# drums.net
KiCad netlist of a schematic drawn in EAGLE
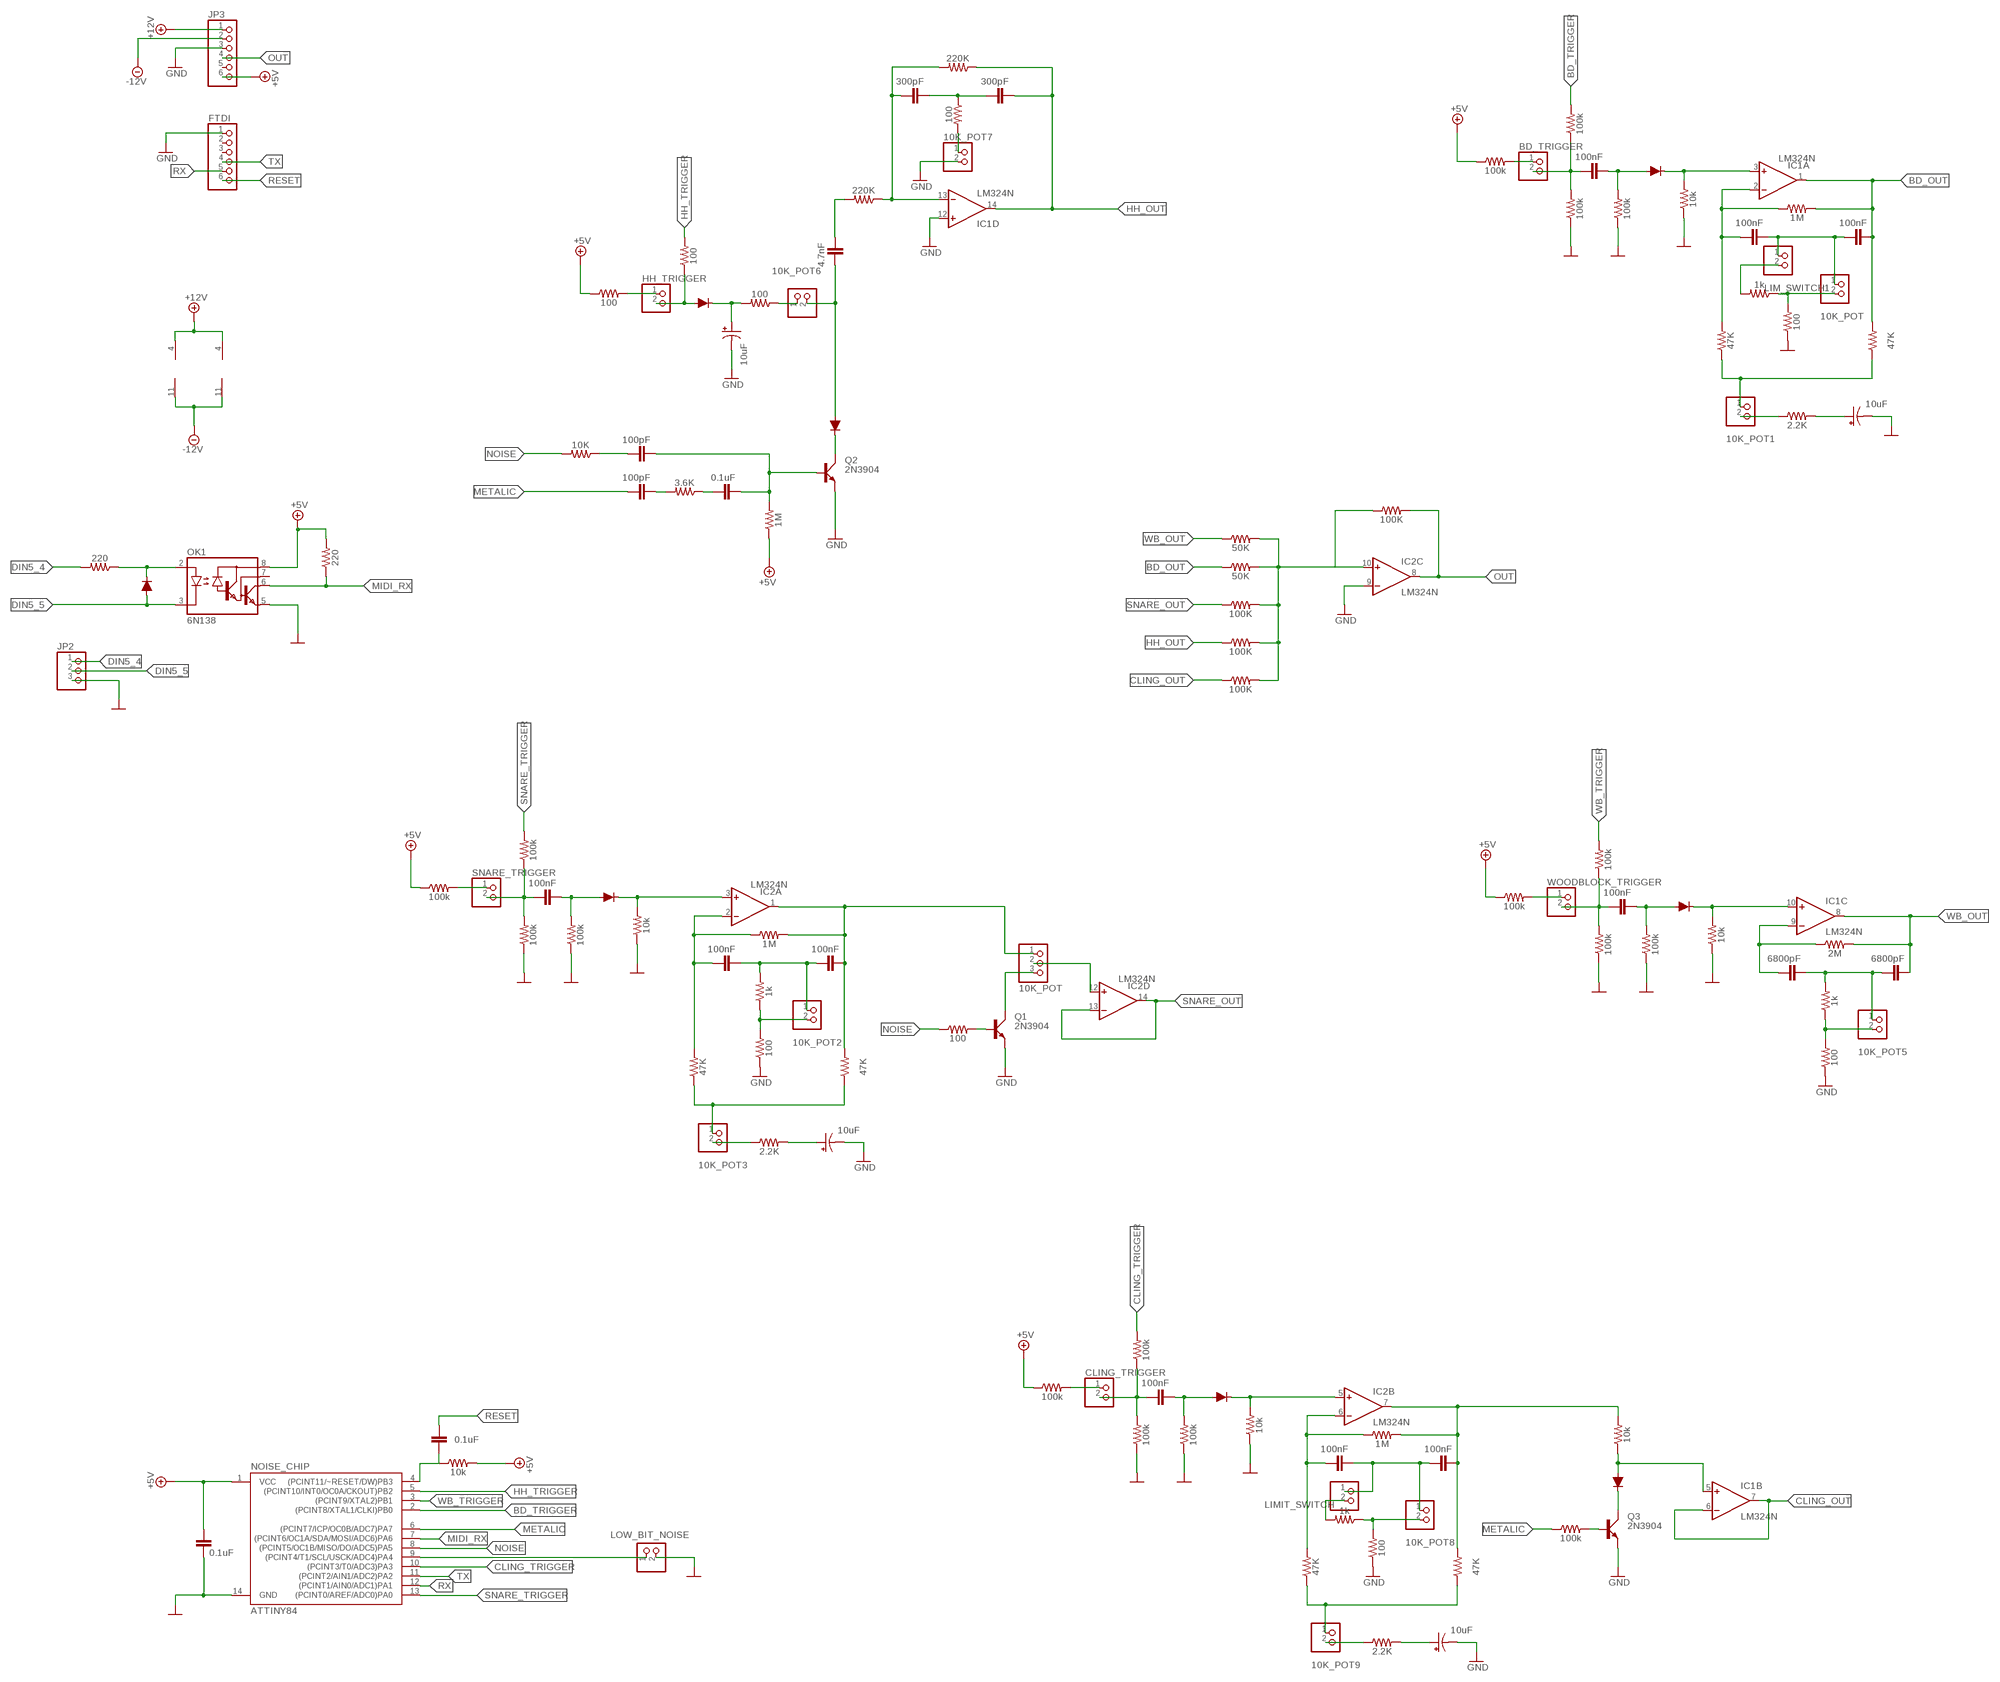
[diagram p0: schematic, sheet 1]

(export (version "E")
  (design (tool "Eeschema 10.0.6"))
  (components
    (comp (ref "1M")
      (value "1M")
      (footprint "eagle-import:AXIAL-0.3")
      (libsource (lib "eagle-import") (part "100KOHM-HORIZ-1/4W-5%"))
    )
    (comp (ref "1M1")
      (value "220")
      (footprint "eagle-import:AXIAL-0.3")
      (libsource (lib "eagle-import") (part "100KOHM-HORIZ-1/4W-5%"))
    )
    (comp (ref "1M2")
      (value "220")
      (footprint "eagle-import:AXIAL-0.3")
      (libsource (lib "eagle-import") (part "100KOHM-HORIZ-1/4W-5%"))
    )
    (comp (ref "10K_POT")
      (value "PINHD-1X2")
      (footprint "eagle-import:1X02")
      (libsource (lib "eagle-import") (part "PINHD-1X2"))
    )
    (comp (ref "10K_POT1")
      (value "PINHD-1X2")
      (footprint "eagle-import:1X02")
      (libsource (lib "eagle-import") (part "PINHD-1X2"))
    )
    (comp (ref "10K_POT2")
      (value "PINHD-1X2")
      (footprint "eagle-import:1X02")
      (libsource (lib "eagle-import") (part "PINHD-1X2"))
    )
    (comp (ref "10K_POT3")
      (value "PINHD-1X2")
      (footprint "eagle-import:1X02")
      (libsource (lib "eagle-import") (part "PINHD-1X2"))
    )
    (comp (ref "10K_POT4")
      (value "10K_POT")
      (footprint "eagle-import:1X03")
      (libsource (lib "eagle-import") (part "pinhead_325_PINHD-1X3"))
    )
    (comp (ref "10K_POT5")
      (value "PINHD-1X2")
      (footprint "eagle-import:1X02")
      (libsource (lib "eagle-import") (part "PINHD-1X2"))
    )
    (comp (ref "10K_POT6")
      (value "PINHD-1X2")
      (footprint "eagle-import:1X02")
      (libsource (lib "eagle-import") (part "PINHD-1X2"))
    )
    (comp (ref "10K_POT7")
      (value "PINHD-1X2")
      (footprint "eagle-import:1X02")
      (libsource (lib "eagle-import") (part "PINHD-1X2"))
    )
    (comp (ref "10K_POT8")
      (value "PINHD-1X2")
      (footprint "eagle-import:1X02")
      (libsource (lib "eagle-import") (part "PINHD-1X2"))
    )
    (comp (ref "10K_POT9")
      (value "PINHD-1X2")
      (footprint "eagle-import:1X02")
      (libsource (lib "eagle-import") (part "PINHD-1X2"))
    )
    (comp (ref "BD_TRIGGER")
      (value "PINHD-1X2")
      (footprint "eagle-import:1X02")
      (libsource (lib "eagle-import") (part "PINHD-1X2"))
    )
    (comp (ref "C1")
      (value "0.1uF")
      (footprint "eagle-import:C5B3")
      (libsource (lib "eagle-import") (part "C5/3"))
    )
    (comp (ref "C2")
      (value "100nF")
      (footprint "eagle-import:C5B3")
      (libsource (lib "eagle-import") (part "C5/3"))
    )
    (comp (ref "C3")
      (value "100nF")
      (footprint "eagle-import:C5B3")
      (libsource (lib "eagle-import") (part "C5/3"))
    )
    (comp (ref "C4")
      (value "0.1uF")
      (footprint "eagle-import:C5B3")
      (libsource (lib "eagle-import") (part "C5/3"))
    )
    (comp (ref "C5")
      (value "10uF")
      (footprint "eagle-import:TT5D11")
      (libsource (lib "eagle-import") (part "CPOL-USTT5D11"))
    )
    (comp (ref "C6")
      (value "100nF")
      (footprint "eagle-import:C5B3")
      (libsource (lib "eagle-import") (part "C5/3"))
    )
    (comp (ref "C7")
      (value "100nF")
      (footprint "eagle-import:C5B3")
      (libsource (lib "eagle-import") (part "C5/3"))
    )
    (comp (ref "C8")
      (value "10uF")
      (footprint "eagle-import:TT5D11")
      (libsource (lib "eagle-import") (part "CPOL-USTT5D11"))
    )
    (comp (ref "C9")
      (value "6800pF")
      (footprint "eagle-import:C5B3")
      (libsource (lib "eagle-import") (part "C5/3"))
    )
    (comp (ref "C10")
      (value "6800pF")
      (footprint "eagle-import:C5B3")
      (libsource (lib "eagle-import") (part "C5/3"))
    )
    (comp (ref "C11")
      (value "10uF")
      (footprint "eagle-import:TT5D11")
      (libsource (lib "eagle-import") (part "CPOL-USTT5D11"))
    )
    (comp (ref "C12")
      (value "0.1uF")
      (footprint "eagle-import:C5B3")
      (libsource (lib "eagle-import") (part "C5/3"))
    )
    (comp (ref "C13")
      (value "100pF")
      (footprint "eagle-import:C5B3")
      (libsource (lib "eagle-import") (part "C5/3"))
    )
    (comp (ref "C14")
      (value "100pF")
      (footprint "eagle-import:C5B3")
      (libsource (lib "eagle-import") (part "C5/3"))
    )
    (comp (ref "C15")
      (value "4.7nF")
      (footprint "eagle-import:C5B3")
      (libsource (lib "eagle-import") (part "C5/3"))
    )
    (comp (ref "C16")
      (value "300pF")
      (footprint "eagle-import:C5B3")
      (libsource (lib "eagle-import") (part "C5/3"))
    )
    (comp (ref "C17")
      (value "300pF")
      (footprint "eagle-import:C5B3")
      (libsource (lib "eagle-import") (part "C5/3"))
    )
    (comp (ref "C18")
      (value "100nF")
      (footprint "eagle-import:C5B3")
      (libsource (lib "eagle-import") (part "C5/3"))
    )
    (comp (ref "C19")
      (value "100nF")
      (footprint "eagle-import:C5B3")
      (libsource (lib "eagle-import") (part "C5/3"))
    )
    (comp (ref "C20")
      (value "100nF")
      (footprint "eagle-import:C5B3")
      (libsource (lib "eagle-import") (part "C5/3"))
    )
    (comp (ref "C21")
      (value "100nF")
      (footprint "eagle-import:C5B3")
      (libsource (lib "eagle-import") (part "C5/3"))
    )
    (comp (ref "C22")
      (value "100nF")
      (footprint "eagle-import:C5B3")
      (libsource (lib "eagle-import") (part "C5/3"))
    )
    (comp (ref "C23")
      (value "10uF")
      (footprint "eagle-import:TT5D11")
      (libsource (lib "eagle-import") (part "CPOL-USTT5D11"))
    )
    (comp (ref "C24")
      (value "100nF")
      (footprint "eagle-import:C5B3")
      (libsource (lib "eagle-import") (part "C5/3"))
    )
    (comp (ref "CLING_TRIGGER")
      (value "PINHD-1X2")
      (footprint "eagle-import:1X02")
      (libsource (lib "eagle-import") (part "PINHD-1X2"))
    )
    (comp (ref "D1")
      (value "1A/50V/1.1V")
      (footprint "eagle-import:DIODE-1N4001-KIT")
      (libsource (lib "eagle-import") (part "DIODE-KIT2"))
    )
    (comp (ref "D2")
      (value "1A/50V/1.1V")
      (footprint "eagle-import:DIODE-1N4001-KIT")
      (libsource (lib "eagle-import") (part "DIODE-KIT2"))
    )
    (comp (ref "D3")
      (value "1A/50V/1.1V")
      (footprint "eagle-import:DIODE-1N4001-KIT")
      (libsource (lib "eagle-import") (part "DIODE-KIT2"))
    )
    (comp (ref "D4")
      (value "1A/50V/1.1V")
      (footprint "eagle-import:DIODE-1N4001-KIT")
      (libsource (lib "eagle-import") (part "DIODE-KIT2"))
    )
    (comp (ref "D5")
      (value "1A/50V/1.1V")
      (footprint "eagle-import:DIODE-1N4001-KIT")
      (libsource (lib "eagle-import") (part "DIODE-KIT2"))
    )
    (comp (ref "D6")
      (value "1A/50V/1.1V")
      (footprint "eagle-import:DIODE-1N4001-KIT")
      (libsource (lib "eagle-import") (part "DIODE-KIT2"))
    )
    (comp (ref "D7")
      (value "1A/50V/1.1V")
      (footprint "eagle-import:DIODE-1N4001-KIT")
      (libsource (lib "eagle-import") (part "DIODE-KIT2"))
    )
    (comp (ref "D8")
      (value "1A/50V/1.1V")
      (footprint "eagle-import:DIODE-1N4001-KIT")
      (libsource (lib "eagle-import") (part "DIODE-KIT2"))
    )
    (comp (ref "FTDI")
      (value "PINHD-1X6")
      (footprint "eagle-import:1X06")
      (libsource (lib "eagle-import") (part "PINHD-1X6"))
    )
    (comp (ref "HH_TRIGGER")
      (value "PINHD-1X2")
      (footprint "eagle-import:1X02")
      (libsource (lib "eagle-import") (part "PINHD-1X2"))
    )
    (comp (ref "IC1")
      (value "LM324N")
      (footprint "eagle-import:DIL14")
      (libsource (lib "eagle-import") (part "LM324N"))
    )
    (comp (ref "IC2")
      (value "LM324N")
      (footprint "eagle-import:DIL14")
      (libsource (lib "eagle-import") (part "LM324N"))
    )
    (comp (ref "JP2")
      (value "PINHD-1X3")
      (footprint "eagle-import:1X03")
      (libsource (lib "eagle-import") (part "PINHD-1X3"))
    )
    (comp (ref "JP3")
      (value "PINHD-1X6")
      (footprint "eagle-import:1X06")
      (libsource (lib "eagle-import") (part "PINHD-1X6"))
    )
    (comp (ref "LIMIT_SWITCH")
      (value "PINHD-1X2")
      (footprint "eagle-import:1X02")
      (libsource (lib "eagle-import") (part "PINHD-1X2"))
    )
    (comp (ref "LIM_SWITCH1")
      (value "PINHD-1X2")
      (footprint "eagle-import:1X02")
      (libsource (lib "eagle-import") (part "PINHD-1X2"))
    )
    (comp (ref "LOW_BIT_NOISE")
      (value "PINHD-1X2")
      (footprint "eagle-import:1X02")
      (libsource (lib "eagle-import") (part "PINHD-1X2"))
    )
    (comp (ref "NOISE_CHIP")
      (value "ATTINY84")
      (footprint "eagle-import:DIP14")
      (libsource (lib "eagle-import") (part "ATTINY84ATTINY84-20PU"))
    )
    (comp (ref "OK1")
      (value "6N138")
      (footprint "eagle-import:DIL08")
      (fields (field (name "MF") "VISHAY/TELEFUNKEN"))
      (libsource (lib "eagle-import") (part "6N138"))
    )
    (comp (ref "Q1")
      (value "2N3904")
      (footprint "eagle-import:TO92D")
      (libsource (lib "eagle-import") (part "2N3904"))
    )
    (comp (ref "Q2")
      (value "2N3904")
      (footprint "eagle-import:TO92D")
      (libsource (lib "eagle-import") (part "2N3904"))
    )
    (comp (ref "Q3")
      (value "2N3904")
      (footprint "eagle-import:TO92D")
      (libsource (lib "eagle-import") (part "2N3904"))
    )
    (comp (ref "R1")
      (value "100k")
      (footprint "eagle-import:AXIAL-0.3")
      (libsource (lib "eagle-import") (part "100KOHM-HORIZ-1/4W-5%"))
    )
    (comp (ref "R2")
      (value "10k")
      (footprint "eagle-import:AXIAL-0.3")
      (libsource (lib "eagle-import") (part "100KOHM-HORIZ-1/4W-5%"))
    )
    (comp (ref "R3")
      (value "1M")
      (footprint "eagle-import:AXIAL-0.3")
      (libsource (lib "eagle-import") (part "100KOHM-HORIZ-1/4W-5%"))
    )
    (comp (ref "R4")
      (value "47K")
      (footprint "eagle-import:AXIAL-0.3")
      (libsource (lib "eagle-import") (part "100KOHM-HORIZ-1/4W-5%"))
    )
    (comp (ref "R5")
      (value "47K")
      (footprint "eagle-import:AXIAL-0.3")
      (libsource (lib "eagle-import") (part "100KOHM-HORIZ-1/4W-5%"))
    )
    (comp (ref "R6")
      (value "1k")
      (footprint "eagle-import:AXIAL-0.3")
      (libsource (lib "eagle-import") (part "100KOHM-HORIZ-1/4W-5%"))
    )
    (comp (ref "R7")
      (value "100")
      (footprint "eagle-import:AXIAL-0.3")
      (libsource (lib "eagle-import") (part "100KOHM-HORIZ-1/4W-5%"))
    )
    (comp (ref "R8")
      (value "2.2K")
      (footprint "eagle-import:AXIAL-0.3")
      (libsource (lib "eagle-import") (part "100KOHM-HORIZ-1/4W-5%"))
    )
    (comp (ref "R9")
      (value "50K")
      (footprint "eagle-import:AXIAL-0.3")
      (libsource (lib "eagle-import") (part "100KOHM-HORIZ-1/4W-5%"))
    )
    (comp (ref "R10")
      (value "100K")
      (footprint "eagle-import:AXIAL-0.3")
      (libsource (lib "eagle-import") (part "100KOHM-HORIZ-1/4W-5%"))
    )
    (comp (ref "R11")
      (value "100")
      (footprint "eagle-import:AXIAL-0.3")
      (libsource (lib "eagle-import") (part "100KOHM-HORIZ-1/4W-5%"))
    )
    (comp (ref "R12")
      (value "100k")
      (footprint "eagle-import:AXIAL-0.3")
      (libsource (lib "eagle-import") (part "100KOHM-HORIZ-1/4W-5%"))
    )
    (comp (ref "R13")
      (value "1M")
      (footprint "eagle-import:AXIAL-0.3")
      (libsource (lib "eagle-import") (part "100KOHM-HORIZ-1/4W-5%"))
    )
    (comp (ref "R14")
      (value "47K")
      (footprint "eagle-import:AXIAL-0.3")
      (libsource (lib "eagle-import") (part "100KOHM-HORIZ-1/4W-5%"))
    )
    (comp (ref "R15")
      (value "47K")
      (footprint "eagle-import:AXIAL-0.3")
      (libsource (lib "eagle-import") (part "100KOHM-HORIZ-1/4W-5%"))
    )
    (comp (ref "R16")
      (value "1k")
      (footprint "eagle-import:AXIAL-0.3")
      (libsource (lib "eagle-import") (part "100KOHM-HORIZ-1/4W-5%"))
    )
    (comp (ref "R17")
      (value "100")
      (footprint "eagle-import:AXIAL-0.3")
      (libsource (lib "eagle-import") (part "100KOHM-HORIZ-1/4W-5%"))
    )
    (comp (ref "R18")
      (value "2.2K")
      (footprint "eagle-import:AXIAL-0.3")
      (libsource (lib "eagle-import") (part "100KOHM-HORIZ-1/4W-5%"))
    )
    (comp (ref "R19")
      (value "100k")
      (footprint "eagle-import:AXIAL-0.3")
      (libsource (lib "eagle-import") (part "100KOHM-HORIZ-1/4W-5%"))
    )
    (comp (ref "R20")
      (value "100k")
      (footprint "eagle-import:AXIAL-0.3")
      (libsource (lib "eagle-import") (part "100KOHM-HORIZ-1/4W-5%"))
    )
    (comp (ref "R21")
      (value "100")
      (footprint "eagle-import:AXIAL-0.3")
      (libsource (lib "eagle-import") (part "100KOHM-HORIZ-1/4W-5%"))
    )
    (comp (ref "R22")
      (value "10k")
      (footprint "eagle-import:AXIAL-0.3")
      (libsource (lib "eagle-import") (part "100KOHM-HORIZ-1/4W-5%"))
    )
    (comp (ref "R23")
      (value "100k")
      (footprint "eagle-import:AXIAL-0.3")
      (libsource (lib "eagle-import") (part "100KOHM-HORIZ-1/4W-5%"))
    )
    (comp (ref "R24")
      (value "2M")
      (footprint "eagle-import:AXIAL-0.3")
      (libsource (lib "eagle-import") (part "100KOHM-HORIZ-1/4W-5%"))
    )
    (comp (ref "R25")
      (value "10k")
      (footprint "eagle-import:AXIAL-0.3")
      (libsource (lib "eagle-import") (part "100KOHM-HORIZ-1/4W-5%"))
    )
    (comp (ref "R26")
      (value "100")
      (footprint "eagle-import:AXIAL-0.3")
      (libsource (lib "eagle-import") (part "100KOHM-HORIZ-1/4W-5%"))
    )
    (comp (ref "R27")
      (value "1k")
      (footprint "eagle-import:AXIAL-0.3")
      (libsource (lib "eagle-import") (part "100KOHM-HORIZ-1/4W-5%"))
    )
    (comp (ref "R28")
      (value "100")
      (footprint "eagle-import:AXIAL-0.3")
      (libsource (lib "eagle-import") (part "100KOHM-HORIZ-1/4W-5%"))
    )
    (comp (ref "R29")
      (value "100")
      (footprint "eagle-import:AXIAL-0.3")
      (libsource (lib "eagle-import") (part "100KOHM-HORIZ-1/4W-5%"))
    )
    (comp (ref "R30")
      (value "100K")
      (footprint "eagle-import:AXIAL-0.3")
      (libsource (lib "eagle-import") (part "100KOHM-HORIZ-1/4W-5%"))
    )
    (comp (ref "R31")
      (value "50K")
      (footprint "eagle-import:AXIAL-0.3")
      (libsource (lib "eagle-import") (part "100KOHM-HORIZ-1/4W-5%"))
    )
    (comp (ref "R32")
      (value "3.6K")
      (footprint "eagle-import:AXIAL-0.3")
      (libsource (lib "eagle-import") (part "100KOHM-HORIZ-1/4W-5%"))
    )
    (comp (ref "R33")
      (value "10K")
      (footprint "eagle-import:AXIAL-0.3")
      (libsource (lib "eagle-import") (part "100KOHM-HORIZ-1/4W-5%"))
    )
    (comp (ref "R34")
      (value "220K")
      (footprint "eagle-import:AXIAL-0.3")
      (libsource (lib "eagle-import") (part "100KOHM-HORIZ-1/4W-5%"))
    )
    (comp (ref "R35")
      (value "220K")
      (footprint "eagle-import:AXIAL-0.3")
      (libsource (lib "eagle-import") (part "100KOHM-HORIZ-1/4W-5%"))
    )
    (comp (ref "R36")
      (value "100")
      (footprint "eagle-import:AXIAL-0.3")
      (libsource (lib "eagle-import") (part "100KOHM-HORIZ-1/4W-5%"))
    )
    (comp (ref "R37")
      (value "100K")
      (footprint "eagle-import:AXIAL-0.3")
      (libsource (lib "eagle-import") (part "100KOHM-HORIZ-1/4W-5%"))
    )
    (comp (ref "R38")
      (value "100k")
      (footprint "eagle-import:AXIAL-0.3")
      (libsource (lib "eagle-import") (part "100KOHM-HORIZ-1/4W-5%"))
    )
    (comp (ref "R39")
      (value "100k")
      (footprint "eagle-import:AXIAL-0.3")
      (libsource (lib "eagle-import") (part "100KOHM-HORIZ-1/4W-5%"))
    )
    (comp (ref "R40")
      (value "10k")
      (footprint "eagle-import:AXIAL-0.3")
      (libsource (lib "eagle-import") (part "100KOHM-HORIZ-1/4W-5%"))
    )
    (comp (ref "R41")
      (value "100k")
      (footprint "eagle-import:AXIAL-0.3")
      (libsource (lib "eagle-import") (part "100KOHM-HORIZ-1/4W-5%"))
    )
    (comp (ref "R42")
      (value "100k")
      (footprint "eagle-import:AXIAL-0.3")
      (libsource (lib "eagle-import") (part "100KOHM-HORIZ-1/4W-5%"))
    )
    (comp (ref "R43")
      (value "100k")
      (footprint "eagle-import:AXIAL-0.3")
      (libsource (lib "eagle-import") (part "100KOHM-HORIZ-1/4W-5%"))
    )
    (comp (ref "R44")
      (value "100k")
      (footprint "eagle-import:AXIAL-0.3")
      (libsource (lib "eagle-import") (part "100KOHM-HORIZ-1/4W-5%"))
    )
    (comp (ref "R45")
      (value "100k")
      (footprint "eagle-import:AXIAL-0.3")
      (libsource (lib "eagle-import") (part "100KOHM-HORIZ-1/4W-5%"))
    )
    (comp (ref "R46")
      (value "1M")
      (footprint "eagle-import:AXIAL-0.3")
      (libsource (lib "eagle-import") (part "100KOHM-HORIZ-1/4W-5%"))
    )
    (comp (ref "R47")
      (value "47K")
      (footprint "eagle-import:AXIAL-0.3")
      (libsource (lib "eagle-import") (part "100KOHM-HORIZ-1/4W-5%"))
    )
    (comp (ref "R48")
      (value "47K")
      (footprint "eagle-import:AXIAL-0.3")
      (libsource (lib "eagle-import") (part "100KOHM-HORIZ-1/4W-5%"))
    )
    (comp (ref "R49")
      (value "1k")
      (footprint "eagle-import:AXIAL-0.3")
      (libsource (lib "eagle-import") (part "100KOHM-HORIZ-1/4W-5%"))
    )
    (comp (ref "R50")
      (value "100")
      (footprint "eagle-import:AXIAL-0.3")
      (libsource (lib "eagle-import") (part "100KOHM-HORIZ-1/4W-5%"))
    )
    (comp (ref "R51")
      (value "2.2K")
      (footprint "eagle-import:AXIAL-0.3")
      (libsource (lib "eagle-import") (part "100KOHM-HORIZ-1/4W-5%"))
    )
    (comp (ref "R52")
      (value "100k")
      (footprint "eagle-import:AXIAL-0.3")
      (libsource (lib "eagle-import") (part "100KOHM-HORIZ-1/4W-5%"))
    )
    (comp (ref "R53")
      (value "10k")
      (footprint "eagle-import:AXIAL-0.3")
      (libsource (lib "eagle-import") (part "100KOHM-HORIZ-1/4W-5%"))
    )
    (comp (ref "R54")
      (value "100k")
      (footprint "eagle-import:AXIAL-0.3")
      (libsource (lib "eagle-import") (part "100KOHM-HORIZ-1/4W-5%"))
    )
    (comp (ref "R55")
      (value "100k")
      (footprint "eagle-import:AXIAL-0.3")
      (libsource (lib "eagle-import") (part "100KOHM-HORIZ-1/4W-5%"))
    )
    (comp (ref "R56")
      (value "100k")
      (footprint "eagle-import:AXIAL-0.3")
      (libsource (lib "eagle-import") (part "100KOHM-HORIZ-1/4W-5%"))
    )
    (comp (ref "R57")
      (value "100k")
      (footprint "eagle-import:AXIAL-0.3")
      (libsource (lib "eagle-import") (part "100KOHM-HORIZ-1/4W-5%"))
    )
    (comp (ref "R58")
      (value "100K")
      (footprint "eagle-import:AXIAL-0.3")
      (libsource (lib "eagle-import") (part "100KOHM-HORIZ-1/4W-5%"))
    )
    (comp (ref "R59")
      (value "10k")
      (footprint "eagle-import:AXIAL-0.3")
      (libsource (lib "eagle-import") (part "100KOHM-HORIZ-1/4W-5%"))
    )
    (comp (ref "SNARE_TRIGGER")
      (value "PINHD-1X2")
      (footprint "eagle-import:1X02")
      (libsource (lib "eagle-import") (part "PINHD-1X2"))
    )
    (comp (ref "WOODBLOCK_TRIGGER")
      (value "PINHD-1X2")
      (footprint "eagle-import:1X02")
      (libsource (lib "eagle-import") (part "PINHD-1X2"))
    )
  )
  (nets
    (net (code "1") (name "+5V") (class "Default")
      (node (ref "1M") (pin "P$1") (pinfunction "1_P$1") (pintype "passive"))
      (node (ref "1M1") (pin "P$2") (pinfunction "2_P$2") (pintype "passive"))
      (node (ref "C1") (pin "1") (pinfunction "1_1") (pintype "passive"))
      (node (ref "JP3") (pin "6") (pinfunction "6_6") (pintype "passive"))
      (node (ref "NOISE_CHIP") (pin "1") (pinfunction "VCC_1") (pintype "bidirectional"))
      (node (ref "OK1") (pin "8") (pinfunction "VCC_8") (pintype "passive"))
      (node (ref "R23") (pin "P$1") (pinfunction "1_P$1") (pintype "passive"))
      (node (ref "R25") (pin "P$2") (pinfunction "2_P$2") (pintype "passive"))
      (node (ref "R29") (pin "P$1") (pinfunction "1_P$1") (pintype "passive"))
      (node (ref "R38") (pin "P$1") (pinfunction "1_P$1") (pintype "passive"))
      (node (ref "R41") (pin "P$1") (pinfunction "1_P$1") (pintype "passive"))
      (node (ref "R54") (pin "P$1") (pinfunction "1_P$1") (pintype "passive"))
    )
    (net (code "2") (name "+12V") (class "Default")
      (node (ref "IC1") (pin "4") (pinfunction "V+_4") (pintype "power_in"))
      (node (ref "IC2") (pin "4") (pinfunction "V+_4") (pintype "power_in"))
      (node (ref "JP3") (pin "1") (pinfunction "1_1") (pintype "passive"))
    )
    (net (code "3") (name "-12V") (class "Default")
      (node (ref "IC1") (pin "11") (pinfunction "V-_11") (pintype "power_in"))
      (node (ref "IC2") (pin "11") (pinfunction "V-_11") (pintype "power_in"))
      (node (ref "JP3") (pin "2") (pinfunction "2_2") (pintype "passive"))
    )
    (net (code "4") (name "BD_OUT") (class "Default")
      (node (ref "10K_POT4") (pin "1") (pinfunction "1_1") (pintype "passive"))
      (node (ref "C3") (pin "2") (pinfunction "2_2") (pintype "passive"))
      (node (ref "C7") (pin "2") (pinfunction "2_2") (pintype "passive"))
      (node (ref "IC1") (pin "1") (pinfunction "OUT_1") (pintype "output"))
      (node (ref "IC2") (pin "1") (pinfunction "OUT_1") (pintype "output"))
      (node (ref "R13") (pin "P$2") (pinfunction "2_P$2") (pintype "passive"))
      (node (ref "R15") (pin "P$2") (pinfunction "2_P$2") (pintype "passive"))
      (node (ref "R3") (pin "P$2") (pinfunction "2_P$2") (pintype "passive"))
      (node (ref "R31") (pin "P$1") (pinfunction "1_P$1") (pintype "passive"))
      (node (ref "R5") (pin "P$2") (pinfunction "2_P$2") (pintype "passive"))
    )
    (net (code "5") (name "BD_TRIGGER") (class "Default")
      (node (ref "NOISE_CHIP") (pin "2") (pinfunction "(PCINT8/XTAL1/CLKI)PB0_2") (pintype "bidirectional"))
      (node (ref "R12") (pin "P$2") (pinfunction "2_P$2") (pintype "passive"))
    )
    (net (code "6") (name "CLING_OUT") (class "Default")
      (node (ref "IC1") (pin "6") (pinfunction "-IN_6") (pintype "input"))
      (node (ref "IC1") (pin "7") (pinfunction "OUT_7") (pintype "output"))
      (node (ref "R58") (pin "P$1") (pinfunction "1_P$1") (pintype "passive"))
    )
    (net (code "7") (name "CLING_TRIGGER") (class "Default")
      (node (ref "NOISE_CHIP") (pin "10") (pinfunction "(PCINT3/T0/ADC3)PA3_10") (pintype "bidirectional"))
      (node (ref "R57") (pin "P$2") (pinfunction "2_P$2") (pintype "passive"))
    )
    (net (code "8") (name "DIN5_4") (class "Default")
      (node (ref "1M2") (pin "P$2") (pinfunction "2_P$2") (pintype "passive"))
      (node (ref "JP2") (pin "1") (pinfunction "1_1") (pintype "passive"))
    )
    (net (code "9") (name "DIN5_5") (class "Default")
      (node (ref "D2") (pin "A") (pinfunction "A_A") (pintype "passive"))
      (node (ref "JP2") (pin "2") (pinfunction "2_2") (pintype "passive"))
      (node (ref "OK1") (pin "3") (pinfunction "C_3") (pintype "passive"))
    )
    (net (code "10") (name "GND") (class "Default")
      (node (ref "10K_POT7") (pin "2") (pinfunction "2_2") (pintype "passive"))
      (node (ref "C1") (pin "2") (pinfunction "2_2") (pintype "passive"))
      (node (ref "C11") (pin "-") (pinfunction "-_-") (pintype "passive"))
      (node (ref "C23") (pin "-") (pinfunction "-_-") (pintype "passive"))
      (node (ref "C5") (pin "-") (pinfunction "-_-") (pintype "passive"))
      (node (ref "C8") (pin "-") (pinfunction "-_-") (pintype "passive"))
      (node (ref "FTDI") (pin "1") (pinfunction "1_1") (pintype "passive"))
      (node (ref "IC1") (pin "12") (pinfunction "+IN_12") (pintype "input"))
      (node (ref "IC2") (pin "9") (pinfunction "-IN_9") (pintype "input"))
      (node (ref "JP2") (pin "3") (pinfunction "3_3") (pintype "passive"))
      (node (ref "JP3") (pin "3") (pinfunction "3_3") (pintype "passive"))
      (node (ref "LOW_BIT_NOISE") (pin "2") (pinfunction "2_2") (pintype "passive"))
      (node (ref "NOISE_CHIP") (pin "14") (pinfunction "GND_14") (pintype "bidirectional"))
      (node (ref "OK1") (pin "5") (pinfunction "GND_5") (pintype "passive"))
      (node (ref "Q1") (pin "E") (pinfunction "E_E") (pintype "passive"))
      (node (ref "Q2") (pin "E") (pinfunction "E_E") (pintype "passive"))
      (node (ref "Q3") (pin "E") (pinfunction "E_E") (pintype "passive"))
      (node (ref "R1") (pin "P$1") (pinfunction "1_P$1") (pintype "passive"))
      (node (ref "R17") (pin "P$1") (pinfunction "1_P$1") (pintype "passive"))
      (node (ref "R2") (pin "P$1") (pinfunction "1_P$1") (pintype "passive"))
      (node (ref "R22") (pin "P$1") (pinfunction "1_P$1") (pintype "passive"))
      (node (ref "R28") (pin "P$1") (pinfunction "1_P$1") (pintype "passive"))
      (node (ref "R39") (pin "P$1") (pinfunction "1_P$1") (pintype "passive"))
      (node (ref "R40") (pin "P$1") (pinfunction "1_P$1") (pintype "passive"))
      (node (ref "R42") (pin "P$1") (pinfunction "1_P$1") (pintype "passive"))
      (node (ref "R43") (pin "P$1") (pinfunction "1_P$1") (pintype "passive"))
      (node (ref "R44") (pin "P$1") (pinfunction "1_P$1") (pintype "passive"))
      (node (ref "R45") (pin "P$1") (pinfunction "1_P$1") (pintype "passive"))
      (node (ref "R50") (pin "P$1") (pinfunction "1_P$1") (pintype "passive"))
      (node (ref "R53") (pin "P$1") (pinfunction "1_P$1") (pintype "passive"))
      (node (ref "R55") (pin "P$1") (pinfunction "1_P$1") (pintype "passive"))
      (node (ref "R56") (pin "P$1") (pinfunction "1_P$1") (pintype "passive"))
      (node (ref "R7") (pin "P$1") (pinfunction "1_P$1") (pintype "passive"))
    )
    (net (code "11") (name "HH_OUT") (class "Default")
      (node (ref "C17") (pin "2") (pinfunction "2_2") (pintype "passive"))
      (node (ref "IC1") (pin "14") (pinfunction "OUT_14") (pintype "output"))
      (node (ref "R35") (pin "P$1") (pinfunction "1_P$1") (pintype "passive"))
      (node (ref "R37") (pin "P$1") (pinfunction "1_P$1") (pintype "passive"))
    )
    (net (code "12") (name "HH_TRIGGER") (class "Default")
      (node (ref "NOISE_CHIP") (pin "5") (pinfunction "(PCINT10/INT0/OC0A/CKOUT)PB2_5") (pintype "bidirectional"))
      (node (ref "R11") (pin "P$2") (pinfunction "2_P$2") (pintype "passive"))
    )
    (net (code "13") (name "METALIC") (class "Default")
      (node (ref "C14") (pin "1") (pinfunction "1_1") (pintype "passive"))
      (node (ref "NOISE_CHIP") (pin "6") (pinfunction "(PCINT7/ICP/OC0B/ADC7)PA7_6") (pintype "bidirectional"))
      (node (ref "R52") (pin "P$1") (pinfunction "1_P$1") (pintype "passive"))
    )
    (net (code "14") (name "MIDI_RX") (class "Default")
      (node (ref "1M1") (pin "P$1") (pinfunction "1_P$1") (pintype "passive"))
      (node (ref "NOISE_CHIP") (pin "7") (pinfunction "(PCINT6/OC1A/SDA/MOSI/ADC6)PA6_7") (pintype "bidirectional"))
      (node (ref "OK1") (pin "6") (pinfunction "VO_6") (pintype "passive"))
    )
    (net (code "15") (name "NOISE") (class "Default")
      (node (ref "NOISE_CHIP") (pin "8") (pinfunction "(PCINT5/OC1B/MISO/DO/ADC5)PA5_8") (pintype "bidirectional"))
      (node (ref "R21") (pin "P$1") (pinfunction "1_P$1") (pintype "passive"))
      (node (ref "R33") (pin "P$2") (pinfunction "2_P$2") (pintype "passive"))
    )
    (net (code "16") (name "Net-(1M-2)") (class "Default")
      (node (ref "1M") (pin "P$2") (pinfunction "2_P$2") (pintype "passive"))
      (node (ref "C12") (pin "2") (pinfunction "2_2") (pintype "passive"))
      (node (ref "C13") (pin "2") (pinfunction "2_2") (pintype "passive"))
      (node (ref "Q2") (pin "B") (pinfunction "B_B") (pintype "passive"))
    )
    (net (code "17") (name "Net-(1M2-1)") (class "Default")
      (node (ref "1M2") (pin "P$1") (pinfunction "1_P$1") (pintype "passive"))
      (node (ref "D2") (pin "C") (pinfunction "C_C") (pintype "passive"))
      (node (ref "OK1") (pin "2") (pinfunction "A_2") (pintype "passive"))
    )
    (net (code "18") (name "Net-(10K_POT-Pad1)") (class "Default")
      (node (ref "10K_POT") (pin "1") (pinfunction "1_1") (pintype "passive"))
      (node (ref "C2") (pin "2") (pinfunction "2_2") (pintype "passive"))
      (node (ref "C3") (pin "1") (pinfunction "1_1") (pintype "passive"))
      (node (ref "LIM_SWITCH1") (pin "1") (pinfunction "1_1") (pintype "passive"))
    )
    (net (code "19") (name "Net-(10K_POT4-Pad3)") (class "Default")
      (node (ref "10K_POT4") (pin "3") (pinfunction "3_3") (pintype "passive"))
      (node (ref "Q1") (pin "C") (pinfunction "C_C") (pintype "passive"))
    )
    (net (code "20") (name "Net-(10K_POT6-Pad2)") (class "Default")
      (node (ref "10K_POT6") (pin "2") (pinfunction "2_2") (pintype "passive"))
      (node (ref "C15") (pin "1") (pinfunction "1_1") (pintype "passive"))
      (node (ref "D5") (pin "A") (pinfunction "A_A") (pintype "passive"))
    )
    (net (code "21") (name "Net-(10K_POT8-Pad1)") (class "Default")
      (node (ref "10K_POT8") (pin "1") (pinfunction "1_1") (pintype "passive"))
      (node (ref "C21") (pin "2") (pinfunction "2_2") (pintype "passive"))
      (node (ref "C22") (pin "1") (pinfunction "1_1") (pintype "passive"))
      (node (ref "LIMIT_SWITCH") (pin "1") (pinfunction "1_1") (pintype "passive"))
    )
    (net (code "22") (name "Net-(D5-PadC)") (class "Default")
      (node (ref "D5") (pin "C") (pinfunction "C_C") (pintype "passive"))
      (node (ref "Q2") (pin "C") (pinfunction "C_C") (pintype "passive"))
    )
    (net (code "23") (name "Net-(D8-PadC)") (class "Default")
      (node (ref "D8") (pin "C") (pinfunction "C_C") (pintype "passive"))
      (node (ref "Q3") (pin "C") (pinfunction "C_C") (pintype "passive"))
    )
    (net (code "24") (name "Net-(IC1A-+IN)") (class "Default")
      (node (ref "D1") (pin "C") (pinfunction "C_C") (pintype "passive"))
      (node (ref "IC1") (pin "3") (pinfunction "+IN_3") (pintype "input"))
      (node (ref "R2") (pin "P$2") (pinfunction "2_P$2") (pintype "passive"))
    )
    (net (code "25") (name "Net-(IC1A--IN)") (class "Default")
      (node (ref "C2") (pin "1") (pinfunction "1_1") (pintype "passive"))
      (node (ref "IC1") (pin "2") (pinfunction "-IN_2") (pintype "input"))
      (node (ref "R3") (pin "P$1") (pinfunction "1_P$1") (pintype "passive"))
      (node (ref "R4") (pin "P$2") (pinfunction "2_P$2") (pintype "passive"))
    )
    (net (code "26") (name "Net-(IC1B-+IN)") (class "Default")
      (node (ref "D8") (pin "A") (pinfunction "A_A") (pintype "passive"))
      (node (ref "IC1") (pin "5") (pinfunction "+IN_5") (pintype "input"))
      (node (ref "R59") (pin "P$1") (pinfunction "1_P$1") (pintype "passive"))
    )
    (net (code "27") (name "Net-(IC1C-+IN)") (class "Default")
      (node (ref "D6") (pin "C") (pinfunction "C_C") (pintype "passive"))
      (node (ref "IC1") (pin "10") (pinfunction "+IN_10") (pintype "input"))
      (node (ref "R40") (pin "P$2") (pinfunction "2_P$2") (pintype "passive"))
    )
    (net (code "28") (name "Net-(IC1C--IN)") (class "Default")
      (node (ref "C9") (pin "1") (pinfunction "1_1") (pintype "passive"))
      (node (ref "IC1") (pin "9") (pinfunction "-IN_9") (pintype "input"))
      (node (ref "R24") (pin "P$1") (pinfunction "1_P$1") (pintype "passive"))
    )
    (net (code "29") (name "Net-(IC1D--IN)") (class "Default")
      (node (ref "C16") (pin "1") (pinfunction "1_1") (pintype "passive"))
      (node (ref "IC1") (pin "13") (pinfunction "-IN_13") (pintype "input"))
      (node (ref "R34") (pin "P$1") (pinfunction "1_P$1") (pintype "passive"))
      (node (ref "R35") (pin "P$2") (pinfunction "2_P$2") (pintype "passive"))
    )
    (net (code "30") (name "Net-(IC2A-+IN)") (class "Default")
      (node (ref "D3") (pin "C") (pinfunction "C_C") (pintype "passive"))
      (node (ref "IC2") (pin "3") (pinfunction "+IN_3") (pintype "input"))
      (node (ref "R22") (pin "P$2") (pinfunction "2_P$2") (pintype "passive"))
    )
    (net (code "31") (name "Net-(IC2A--IN)") (class "Default")
      (node (ref "C6") (pin "1") (pinfunction "1_1") (pintype "passive"))
      (node (ref "IC2") (pin "2") (pinfunction "-IN_2") (pintype "input"))
      (node (ref "R13") (pin "P$1") (pinfunction "1_P$1") (pintype "passive"))
      (node (ref "R14") (pin "P$2") (pinfunction "2_P$2") (pintype "passive"))
    )
    (net (code "32") (name "Net-(IC2B-+IN)") (class "Default")
      (node (ref "D7") (pin "C") (pinfunction "C_C") (pintype "passive"))
      (node (ref "IC2") (pin "5") (pinfunction "+IN_5") (pintype "input"))
      (node (ref "R53") (pin "P$2") (pinfunction "2_P$2") (pintype "passive"))
    )
    (net (code "33") (name "Net-(IC2B--IN)") (class "Default")
      (node (ref "C21") (pin "1") (pinfunction "1_1") (pintype "passive"))
      (node (ref "IC2") (pin "6") (pinfunction "-IN_6") (pintype "input"))
      (node (ref "R46") (pin "P$1") (pinfunction "1_P$1") (pintype "passive"))
      (node (ref "R47") (pin "P$2") (pinfunction "2_P$2") (pintype "passive"))
    )
    (net (code "34") (name "Net-(IC2B-OUT)") (class "Default")
      (node (ref "C22") (pin "2") (pinfunction "2_2") (pintype "passive"))
      (node (ref "IC2") (pin "7") (pinfunction "OUT_7") (pintype "output"))
      (node (ref "R46") (pin "P$2") (pinfunction "2_P$2") (pintype "passive"))
      (node (ref "R48") (pin "P$2") (pinfunction "2_P$2") (pintype "passive"))
      (node (ref "R59") (pin "P$2") (pinfunction "2_P$2") (pintype "passive"))
    )
    (net (code "35") (name "Net-(IC2C-+IN)") (class "Default")
      (node (ref "IC2") (pin "10") (pinfunction "+IN_10") (pintype "input"))
      (node (ref "R10") (pin "P$2") (pinfunction "2_P$2") (pintype "passive"))
      (node (ref "R30") (pin "P$1") (pinfunction "1_P$1") (pintype "passive"))
      (node (ref "R31") (pin "P$2") (pinfunction "2_P$2") (pintype "passive"))
      (node (ref "R37") (pin "P$2") (pinfunction "2_P$2") (pintype "passive"))
      (node (ref "R58") (pin "P$2") (pinfunction "2_P$2") (pintype "passive"))
      (node (ref "R9") (pin "P$2") (pinfunction "2_P$2") (pintype "passive"))
    )
    (net (code "36") (name "Net-(IC2D-+IN)") (class "Default")
      (node (ref "10K_POT4") (pin "2") (pinfunction "2_2") (pintype "passive"))
      (node (ref "IC2") (pin "12") (pinfunction "+IN_12") (pintype "input"))
    )
    (net (code "37") (name "Net-(NOISE_CHIP-(PCINT4{slash}T1{slash}SCL{slash}USCK{slash}ADC4)PA4)") (class "Default")
      (node (ref "LOW_BIT_NOISE") (pin "1") (pinfunction "1_1") (pintype "passive"))
      (node (ref "NOISE_CHIP") (pin "9") (pinfunction "(PCINT4/T1/SCL/USCK/ADC4)PA4_9") (pintype "bidirectional"))
    )
    (net (code "38") (name "Net-(NOISE_CHIP-(PCINT11{slash}~{RESET{slash}DW})PB3)") (class "Default")
      (node (ref "C4") (pin "2") (pinfunction "2_2") (pintype "passive"))
      (node (ref "NOISE_CHIP") (pin "4") (pinfunction "(PCINT11/~{RESET/DW})PB3_4") (pintype "bidirectional"))
      (node (ref "R25") (pin "P$1") (pinfunction "1_P$1") (pintype "passive"))
    )
    (net (code "39") (name "Net-(R1-2)") (class "Default")
      (node (ref "C18") (pin "2") (pinfunction "2_2") (pintype "passive"))
      (node (ref "D1") (pin "A") (pinfunction "A_A") (pintype "passive"))
      (node (ref "R1") (pin "P$2") (pinfunction "2_P$2") (pintype "passive"))
    )
    (net (code "40") (name "Net-(R4-1)") (class "Default")
      (node (ref "10K_POT1") (pin "1") (pinfunction "1_1") (pintype "passive"))
      (node (ref "R4") (pin "P$1") (pinfunction "1_P$1") (pintype "passive"))
      (node (ref "R5") (pin "P$1") (pinfunction "1_P$1") (pintype "passive"))
    )
    (net (code "41") (name "Net-(R6-1)") (class "Default")
      (node (ref "10K_POT") (pin "2") (pinfunction "2_2") (pintype "passive"))
      (node (ref "R6") (pin "P$1") (pinfunction "1_P$1") (pintype "passive"))
      (node (ref "R7") (pin "P$2") (pinfunction "2_P$2") (pintype "passive"))
    )
    (net (code "42") (name "Net-(R6-2)") (class "Default")
      (node (ref "LIM_SWITCH1") (pin "2") (pinfunction "2_2") (pintype "passive"))
      (node (ref "R6") (pin "P$2") (pinfunction "2_P$2") (pintype "passive"))
    )
    (net (code "43") (name "Net-(R8-1)") (class "Default")
      (node (ref "10K_POT1") (pin "2") (pinfunction "2_2") (pintype "passive"))
      (node (ref "R8") (pin "P$1") (pinfunction "1_P$1") (pintype "passive"))
    )
    (net (code "44") (name "Net-(R8-2)") (class "Default")
      (node (ref "C5") (pin "+") (pinfunction "+_+") (pintype "passive"))
      (node (ref "R8") (pin "P$2") (pinfunction "2_P$2") (pintype "passive"))
    )
    (net (code "45") (name "Net-(R11-1)") (class "Default")
      (node (ref "D4") (pin "A") (pinfunction "A_A") (pintype "passive"))
      (node (ref "HH_TRIGGER") (pin "2") (pinfunction "2_2") (pintype "passive"))
      (node (ref "R11") (pin "P$1") (pinfunction "1_P$1") (pintype "passive"))
    )
    (net (code "46") (name "Net-(R12-1)") (class "Default")
      (node (ref "BD_TRIGGER") (pin "2") (pinfunction "2_2") (pintype "passive"))
      (node (ref "C18") (pin "1") (pinfunction "1_1") (pintype "passive"))
      (node (ref "R12") (pin "P$1") (pinfunction "1_P$1") (pintype "passive"))
      (node (ref "R39") (pin "P$2") (pinfunction "2_P$2") (pintype "passive"))
    )
    (net (code "47") (name "Net-(R14-1)") (class "Default")
      (node (ref "10K_POT3") (pin "1") (pinfunction "1_1") (pintype "passive"))
      (node (ref "R14") (pin "P$1") (pinfunction "1_P$1") (pintype "passive"))
      (node (ref "R15") (pin "P$1") (pinfunction "1_P$1") (pintype "passive"))
    )
    (net (code "48") (name "Net-(R16-1)") (class "Default")
      (node (ref "10K_POT2") (pin "2") (pinfunction "2_2") (pintype "passive"))
      (node (ref "R16") (pin "P$1") (pinfunction "1_P$1") (pintype "passive"))
      (node (ref "R17") (pin "P$2") (pinfunction "2_P$2") (pintype "passive"))
    )
    (net (code "49") (name "Net-(R16-2)") (class "Default")
      (node (ref "10K_POT2") (pin "1") (pinfunction "1_1") (pintype "passive"))
      (node (ref "C6") (pin "2") (pinfunction "2_2") (pintype "passive"))
      (node (ref "C7") (pin "1") (pinfunction "1_1") (pintype "passive"))
      (node (ref "R16") (pin "P$2") (pinfunction "2_P$2") (pintype "passive"))
    )
    (net (code "50") (name "Net-(R18-1)") (class "Default")
      (node (ref "10K_POT3") (pin "2") (pinfunction "2_2") (pintype "passive"))
      (node (ref "R18") (pin "P$1") (pinfunction "1_P$1") (pintype "passive"))
    )
    (net (code "51") (name "Net-(R18-2)") (class "Default")
      (node (ref "C8") (pin "+") (pinfunction "+_+") (pintype "passive"))
      (node (ref "R18") (pin "P$2") (pinfunction "2_P$2") (pintype "passive"))
    )
    (net (code "52") (name "Net-(R19-1)") (class "Default")
      (node (ref "C19") (pin "1") (pinfunction "1_1") (pintype "passive"))
      (node (ref "R19") (pin "P$1") (pinfunction "1_P$1") (pintype "passive"))
      (node (ref "R42") (pin "P$2") (pinfunction "2_P$2") (pintype "passive"))
      (node (ref "WOODBLOCK_TRIGGER") (pin "2") (pinfunction "2_2") (pintype "passive"))
    )
    (net (code "53") (name "Net-(R20-1)") (class "Default")
      (node (ref "C20") (pin "1") (pinfunction "1_1") (pintype "passive"))
      (node (ref "R20") (pin "P$1") (pinfunction "1_P$1") (pintype "passive"))
      (node (ref "R44") (pin "P$2") (pinfunction "2_P$2") (pintype "passive"))
      (node (ref "SNARE_TRIGGER") (pin "2") (pinfunction "2_2") (pintype "passive"))
    )
    (net (code "54") (name "Net-(R21-2)") (class "Default")
      (node (ref "Q1") (pin "B") (pinfunction "B_B") (pintype "passive"))
      (node (ref "R21") (pin "P$2") (pinfunction "2_P$2") (pintype "passive"))
    )
    (net (code "55") (name "Net-(R23-2)") (class "Default")
      (node (ref "R23") (pin "P$2") (pinfunction "2_P$2") (pintype "passive"))
      (node (ref "SNARE_TRIGGER") (pin "1") (pinfunction "1_1") (pintype "passive"))
    )
    (net (code "56") (name "Net-(R26-1)") (class "Default")
      (node (ref "10K_POT6") (pin "1") (pinfunction "1_1") (pintype "passive"))
      (node (ref "R26") (pin "P$1") (pinfunction "1_P$1") (pintype "passive"))
    )
    (net (code "57") (name "Net-(R26-2)") (class "Default")
      (node (ref "C11") (pin "+") (pinfunction "+_+") (pintype "passive"))
      (node (ref "D4") (pin "C") (pinfunction "C_C") (pintype "passive"))
      (node (ref "R26") (pin "P$2") (pinfunction "2_P$2") (pintype "passive"))
    )
    (net (code "58") (name "Net-(R27-1)") (class "Default")
      (node (ref "10K_POT5") (pin "2") (pinfunction "2_2") (pintype "passive"))
      (node (ref "R27") (pin "P$1") (pinfunction "1_P$1") (pintype "passive"))
      (node (ref "R28") (pin "P$2") (pinfunction "2_P$2") (pintype "passive"))
    )
    (net (code "59") (name "Net-(R27-2)") (class "Default")
      (node (ref "10K_POT5") (pin "1") (pinfunction "1_1") (pintype "passive"))
      (node (ref "C10") (pin "1") (pinfunction "1_1") (pintype "passive"))
      (node (ref "C9") (pin "2") (pinfunction "2_2") (pintype "passive"))
      (node (ref "R27") (pin "P$2") (pinfunction "2_P$2") (pintype "passive"))
    )
    (net (code "60") (name "Net-(R29-2)") (class "Default")
      (node (ref "HH_TRIGGER") (pin "1") (pinfunction "1_1") (pintype "passive"))
      (node (ref "R29") (pin "P$2") (pinfunction "2_P$2") (pintype "passive"))
    )
    (net (code "61") (name "Net-(R32-1)") (class "Default")
      (node (ref "C12") (pin "1") (pinfunction "1_1") (pintype "passive"))
      (node (ref "R32") (pin "P$1") (pinfunction "1_P$1") (pintype "passive"))
    )
    (net (code "62") (name "Net-(R32-2)") (class "Default")
      (node (ref "C14") (pin "2") (pinfunction "2_2") (pintype "passive"))
      (node (ref "R32") (pin "P$2") (pinfunction "2_P$2") (pintype "passive"))
    )
    (net (code "63") (name "Net-(R33-1)") (class "Default")
      (node (ref "C13") (pin "1") (pinfunction "1_1") (pintype "passive"))
      (node (ref "R33") (pin "P$1") (pinfunction "1_P$1") (pintype "passive"))
    )
    (net (code "64") (name "Net-(R34-2)") (class "Default")
      (node (ref "C15") (pin "2") (pinfunction "2_2") (pintype "passive"))
      (node (ref "R34") (pin "P$2") (pinfunction "2_P$2") (pintype "passive"))
    )
    (net (code "65") (name "Net-(R36-1)") (class "Default")
      (node (ref "C16") (pin "2") (pinfunction "2_2") (pintype "passive"))
      (node (ref "C17") (pin "1") (pinfunction "1_1") (pintype "passive"))
      (node (ref "R36") (pin "P$1") (pinfunction "1_P$1") (pintype "passive"))
    )
    (net (code "66") (name "Net-(R36-2)") (class "Default")
      (node (ref "10K_POT7") (pin "1") (pinfunction "1_1") (pintype "passive"))
      (node (ref "R36") (pin "P$2") (pinfunction "2_P$2") (pintype "passive"))
    )
    (net (code "67") (name "Net-(R38-2)") (class "Default")
      (node (ref "BD_TRIGGER") (pin "1") (pinfunction "1_1") (pintype "passive"))
      (node (ref "R38") (pin "P$2") (pinfunction "2_P$2") (pintype "passive"))
    )
    (net (code "68") (name "Net-(R41-2)") (class "Default")
      (node (ref "R41") (pin "P$2") (pinfunction "2_P$2") (pintype "passive"))
      (node (ref "WOODBLOCK_TRIGGER") (pin "1") (pinfunction "1_1") (pintype "passive"))
    )
    (net (code "69") (name "Net-(R43-2)") (class "Default")
      (node (ref "C19") (pin "2") (pinfunction "2_2") (pintype "passive"))
      (node (ref "D6") (pin "A") (pinfunction "A_A") (pintype "passive"))
      (node (ref "R43") (pin "P$2") (pinfunction "2_P$2") (pintype "passive"))
    )
    (net (code "70") (name "Net-(R45-2)") (class "Default")
      (node (ref "C20") (pin "2") (pinfunction "2_2") (pintype "passive"))
      (node (ref "D3") (pin "A") (pinfunction "A_A") (pintype "passive"))
      (node (ref "R45") (pin "P$2") (pinfunction "2_P$2") (pintype "passive"))
    )
    (net (code "71") (name "Net-(R47-1)") (class "Default")
      (node (ref "10K_POT9") (pin "1") (pinfunction "1_1") (pintype "passive"))
      (node (ref "R47") (pin "P$1") (pinfunction "1_P$1") (pintype "passive"))
      (node (ref "R48") (pin "P$1") (pinfunction "1_P$1") (pintype "passive"))
    )
    (net (code "72") (name "Net-(R49-1)") (class "Default")
      (node (ref "10K_POT8") (pin "2") (pinfunction "2_2") (pintype "passive"))
      (node (ref "R49") (pin "P$1") (pinfunction "1_P$1") (pintype "passive"))
      (node (ref "R50") (pin "P$2") (pinfunction "2_P$2") (pintype "passive"))
    )
    (net (code "73") (name "Net-(R49-2)") (class "Default")
      (node (ref "LIMIT_SWITCH") (pin "2") (pinfunction "2_2") (pintype "passive"))
      (node (ref "R49") (pin "P$2") (pinfunction "2_P$2") (pintype "passive"))
    )
    (net (code "74") (name "Net-(R51-1)") (class "Default")
      (node (ref "10K_POT9") (pin "2") (pinfunction "2_2") (pintype "passive"))
      (node (ref "R51") (pin "P$1") (pinfunction "1_P$1") (pintype "passive"))
    )
    (net (code "75") (name "Net-(R51-2)") (class "Default")
      (node (ref "C23") (pin "+") (pinfunction "+_+") (pintype "passive"))
      (node (ref "R51") (pin "P$2") (pinfunction "2_P$2") (pintype "passive"))
    )
    (net (code "76") (name "Net-(R52-2)") (class "Default")
      (node (ref "Q3") (pin "B") (pinfunction "B_B") (pintype "passive"))
      (node (ref "R52") (pin "P$2") (pinfunction "2_P$2") (pintype "passive"))
    )
    (net (code "77") (name "Net-(R54-2)") (class "Default")
      (node (ref "CLING_TRIGGER") (pin "1") (pinfunction "1_1") (pintype "passive"))
      (node (ref "R54") (pin "P$2") (pinfunction "2_P$2") (pintype "passive"))
    )
    (net (code "78") (name "Net-(R55-2)") (class "Default")
      (node (ref "C24") (pin "1") (pinfunction "1_1") (pintype "passive"))
      (node (ref "CLING_TRIGGER") (pin "2") (pinfunction "2_2") (pintype "passive"))
      (node (ref "R55") (pin "P$2") (pinfunction "2_P$2") (pintype "passive"))
      (node (ref "R57") (pin "P$1") (pinfunction "1_P$1") (pintype "passive"))
    )
    (net (code "79") (name "Net-(R56-2)") (class "Default")
      (node (ref "C24") (pin "2") (pinfunction "2_2") (pintype "passive"))
      (node (ref "D7") (pin "A") (pinfunction "A_A") (pintype "passive"))
      (node (ref "R56") (pin "P$2") (pinfunction "2_P$2") (pintype "passive"))
    )
    (net (code "80") (name "OUT") (class "Default")
      (node (ref "IC2") (pin "8") (pinfunction "OUT_8") (pintype "output"))
      (node (ref "JP3") (pin "4") (pinfunction "4_4") (pintype "passive"))
      (node (ref "R30") (pin "P$2") (pinfunction "2_P$2") (pintype "passive"))
    )
    (net (code "81") (name "RESET") (class "Default")
      (node (ref "C4") (pin "1") (pinfunction "1_1") (pintype "passive"))
      (node (ref "FTDI") (pin "6") (pinfunction "6_6") (pintype "passive"))
    )
    (net (code "82") (name "RX") (class "Default")
      (node (ref "FTDI") (pin "5") (pinfunction "5_5") (pintype "passive"))
      (node (ref "NOISE_CHIP") (pin "12") (pinfunction "(PCINT1/AIN0/ADC1)PA1_12") (pintype "bidirectional"))
    )
    (net (code "83") (name "SNARE_OUT") (class "Default")
      (node (ref "IC2") (pin "13") (pinfunction "-IN_13") (pintype "input"))
      (node (ref "IC2") (pin "14") (pinfunction "OUT_14") (pintype "output"))
      (node (ref "R10") (pin "P$1") (pinfunction "1_P$1") (pintype "passive"))
    )
    (net (code "84") (name "SNARE_TRIGGER") (class "Default")
      (node (ref "NOISE_CHIP") (pin "13") (pinfunction "(PCINT0/AREF/ADC0)PA0_13") (pintype "bidirectional"))
      (node (ref "R20") (pin "P$2") (pinfunction "2_P$2") (pintype "passive"))
    )
    (net (code "85") (name "TX") (class "Default")
      (node (ref "FTDI") (pin "4") (pinfunction "4_4") (pintype "passive"))
      (node (ref "NOISE_CHIP") (pin "11") (pinfunction "(PCINT2/AIN1/ADC2)PA2_11") (pintype "bidirectional"))
    )
    (net (code "86") (name "WB_OUT") (class "Default")
      (node (ref "C10") (pin "2") (pinfunction "2_2") (pintype "passive"))
      (node (ref "IC1") (pin "8") (pinfunction "OUT_8") (pintype "output"))
      (node (ref "R24") (pin "P$2") (pinfunction "2_P$2") (pintype "passive"))
      (node (ref "R9") (pin "P$1") (pinfunction "1_P$1") (pintype "passive"))
    )
    (net (code "87") (name "WB_TRIGGER") (class "Default")
      (node (ref "NOISE_CHIP") (pin "3") (pinfunction "(PCINT9/XTAL2)PB1_3") (pintype "bidirectional"))
      (node (ref "R19") (pin "P$2") (pinfunction "2_P$2") (pintype "passive"))
    )
    (net (code "88") (name "unconnected-(FTDI-Pad2)") (class "Default")
      (node (ref "FTDI") (pin "2") (pinfunction "2_2") (pintype "passive"))
    )
    (net (code "89") (name "unconnected-(FTDI-Pad3)") (class "Default")
      (node (ref "FTDI") (pin "3") (pinfunction "3_3") (pintype "passive"))
    )
    (net (code "90") (name "unconnected-(JP3-Pad5)") (class "Default")
      (node (ref "JP3") (pin "5") (pinfunction "5_5") (pintype "passive"))
    )
    (net (code "91") (name "unconnected-(OK1-VB-Pad7)") (class "Default")
      (node (ref "OK1") (pin "7") (pinfunction "VB_7") (pintype "passive"))
    )
  )
)
